# SilentStepStick-TMC2130_v11.net
KiCad netlist of a schematic drawn in EAGLE
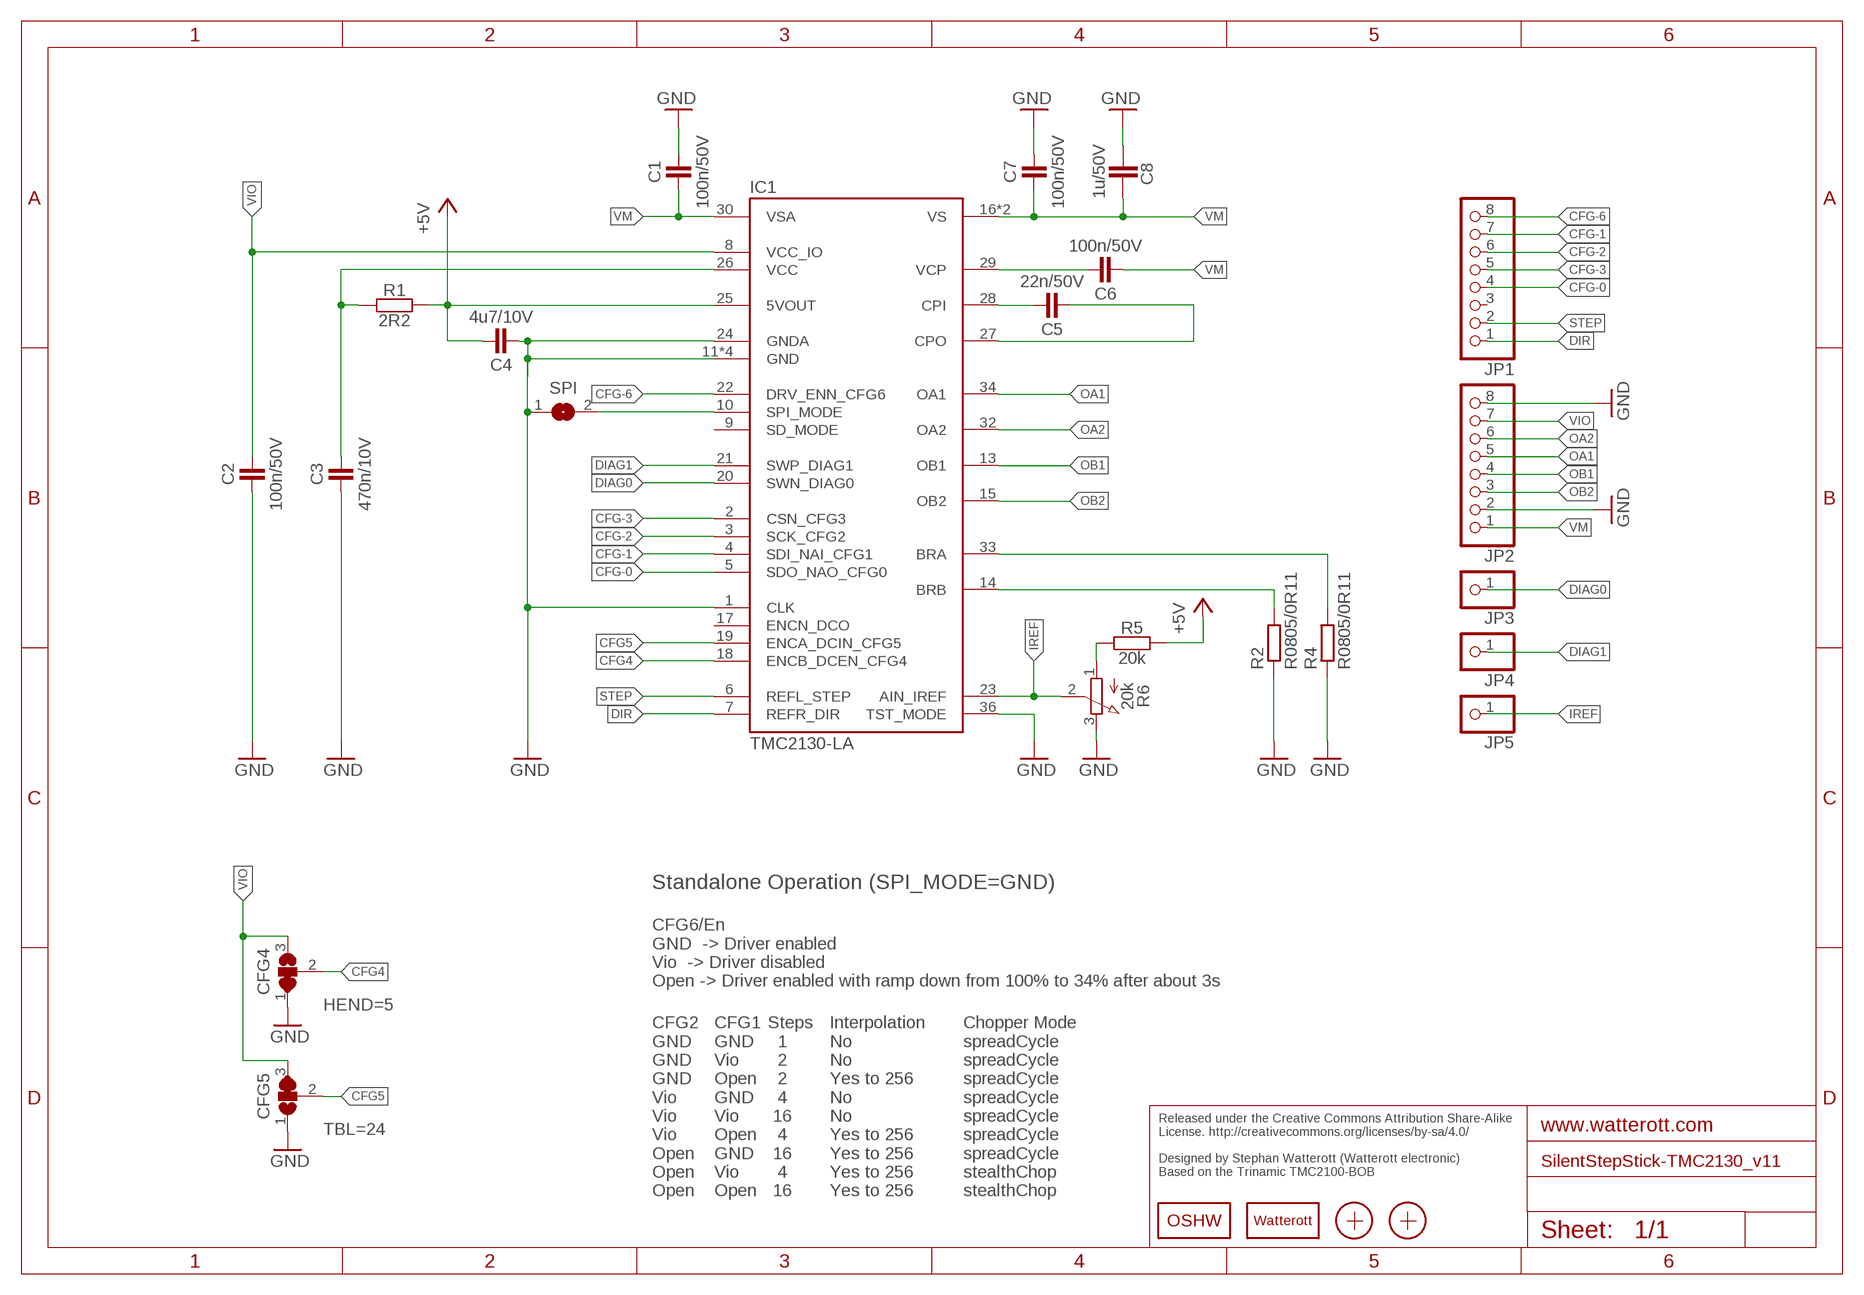
[diagram p0: schematic, sheet 1]

(export (version "E")
  (design (tool "Eeschema 10.0.6"))
  (components
    (comp (ref "C1")
      (value "100n/50V")
      (footprint "eagle-import:C0402")
      (libsource (lib "eagle-import") (part "CAPACITOR-0402"))
    )
    (comp (ref "C2")
      (value "100n/50V")
      (footprint "eagle-import:C0402")
      (libsource (lib "eagle-import") (part "CAPACITOR-0402"))
    )
    (comp (ref "C3")
      (value "470n/10V")
      (footprint "eagle-import:C0402")
      (libsource (lib "eagle-import") (part "CAPACITOR-0402"))
    )
    (comp (ref "C4")
      (value "4u7/10V")
      (footprint "eagle-import:C0402")
      (libsource (lib "eagle-import") (part "CAPACITOR-0402"))
    )
    (comp (ref "C5")
      (value "22n/50V")
      (footprint "eagle-import:C0402")
      (libsource (lib "eagle-import") (part "CAPACITOR-0402"))
    )
    (comp (ref "C6")
      (value "100n/50V")
      (footprint "eagle-import:C0402")
      (libsource (lib "eagle-import") (part "CAPACITOR-0402"))
    )
    (comp (ref "C7")
      (value "100n/50V")
      (footprint "eagle-import:C0402")
      (libsource (lib "eagle-import") (part "CAPACITOR-0402"))
    )
    (comp (ref "C8")
      (value "1u/50V")
      (footprint "eagle-import:C0603")
      (libsource (lib "eagle-import") (part "C-EUC0603"))
    )
    (comp (ref "CFG4")
      (value "JUMPER3-0201")
      (footprint "eagle-import:JUMPER3-0201")
      (libsource (lib "eagle-import") (part "JUMPER3-0201"))
    )
    (comp (ref "CFG5")
      (value "JUMPER3-0201")
      (footprint "eagle-import:JUMPER3-0201")
      (libsource (lib "eagle-import") (part "JUMPER3-0201"))
    )
    (comp (ref "IC1")
      (value "TMC2130-LA")
      (footprint "eagle-import:QFN36-PAD")
      (libsource (lib "eagle-import") (part "TMC21X0-LA"))
    )
    (comp (ref "JP1")
      (value "PINHD-1X08_2.54-S")
      (footprint "eagle-import:1X08-S")
      (libsource (lib "eagle-import") (part "PINHD-1X08_2.54-S"))
    )
    (comp (ref "JP2")
      (value "PINHD-1X08_2.54-S")
      (footprint "eagle-import:1X08-S")
      (libsource (lib "eagle-import") (part "PINHD-1X08_2.54-S"))
    )
    (comp (ref "JP3")
      (value "PINHD-1X1")
      (footprint "eagle-import:1X01")
      (libsource (lib "eagle-import") (part "PINHD-1X1"))
    )
    (comp (ref "JP4")
      (value "PINHD-1X1")
      (footprint "eagle-import:1X01")
      (libsource (lib "eagle-import") (part "PINHD-1X1"))
    )
    (comp (ref "JP5")
      (value "PINHD-1X1")
      (footprint "eagle-import:1X01")
      (libsource (lib "eagle-import") (part "PINHD-1X1"))
    )
    (comp (ref "LOGO1")
      (value "OSHW_LOGOX0070")
      (footprint "eagle-import:OSHW_6X70")
      (libsource (lib "eagle-import") (part "OSHW_LOGOX0070"))
    )
    (comp (ref "LOGO2")
      (value "LOGO-S_PLACE_M")
      (footprint "eagle-import:SPARK_TPLACE_M")
      (libsource (lib "eagle-import") (part "LOGO-S_PLACE_M"))
    )
    (comp (ref "R1")
      (value "2R2")
      (footprint "eagle-import:C0402")
      (libsource (lib "eagle-import") (part "RESISTOR-0402"))
    )
    (comp (ref "R2")
      (value "R0805/0R11")
      (footprint "eagle-import:M0805")
      (libsource (lib "eagle-import") (part "R-EU_M0805"))
    )
    (comp (ref "R4")
      (value "R0805/0R11")
      (footprint "eagle-import:M0805")
      (libsource (lib "eagle-import") (part "R-EU_M0805"))
    )
    (comp (ref "R5")
      (value "20k")
      (footprint "eagle-import:C0402")
      (libsource (lib "eagle-import") (part "RESISTOR-0402"))
    )
    (comp (ref "R6")
      (value "20k")
      (footprint "eagle-import:POT_EVM3R")
      (libsource (lib "eagle-import") (part "POT-EVM3R"))
    )
    (comp (ref "SPI")
      (value "JUMPER2-0402-NC")
      (footprint "eagle-import:JUMPER2-0402_NC")
      (libsource (lib "eagle-import") (part "JUMPER2-0402-NC"))
    )
    (comp (ref "X1")
      (value "PASSER-07")
      (footprint "eagle-import:PASSER_07MM")
      (libsource (lib "eagle-import") (part "PASSER-07"))
    )
    (comp (ref "X2")
      (value "PASSER-07")
      (footprint "eagle-import:PASSER_07MM")
      (libsource (lib "eagle-import") (part "PASSER-07"))
    )
  )
  (nets
    (net (code "1") (name "+5V") (class "Default")
      (node (ref "C4") (pin "2") (pinfunction "2_2") (pintype "passive"))
      (node (ref "IC1") (pin "25") (pinfunction "5VOUT_25") (pintype "power_in"))
      (node (ref "R1") (pin "2") (pinfunction "2_2") (pintype "passive"))
      (node (ref "R5") (pin "2") (pinfunction "2_2") (pintype "passive"))
    )
    (net (code "2") (name "CFG-0") (class "Default")
      (node (ref "IC1") (pin "5") (pinfunction "SDO_NAO_CFG0_5") (pintype "bidirectional"))
      (node (ref "JP1") (pin "4") (pinfunction "4_4") (pintype "passive"))
    )
    (net (code "3") (name "CFG-1") (class "Default")
      (node (ref "IC1") (pin "4") (pinfunction "SDI_NAI_CFG1_4") (pintype "bidirectional"))
      (node (ref "JP1") (pin "7") (pinfunction "7_7") (pintype "passive"))
    )
    (net (code "4") (name "CFG-2") (class "Default")
      (node (ref "IC1") (pin "3") (pinfunction "SCK_CFG2_3") (pintype "bidirectional"))
      (node (ref "JP1") (pin "6") (pinfunction "6_6") (pintype "passive"))
    )
    (net (code "5") (name "CFG-3") (class "Default")
      (node (ref "IC1") (pin "2") (pinfunction "CSN_CFG3_2") (pintype "bidirectional"))
      (node (ref "JP1") (pin "5") (pinfunction "5_5") (pintype "passive"))
    )
    (net (code "6") (name "CFG-6") (class "Default")
      (node (ref "IC1") (pin "22") (pinfunction "DRV_ENN_CFG6_22") (pintype "bidirectional"))
      (node (ref "JP1") (pin "8") (pinfunction "8_8") (pintype "passive"))
    )
    (net (code "7") (name "CFG4") (class "Default")
      (node (ref "CFG4") (pin "2") (pinfunction "2_2") (pintype "passive"))
      (node (ref "IC1") (pin "18") (pinfunction "ENCB_DCEN_CFG4_18") (pintype "bidirectional"))
    )
    (net (code "8") (name "CFG5") (class "Default")
      (node (ref "CFG5") (pin "2") (pinfunction "2_2") (pintype "passive"))
      (node (ref "IC1") (pin "19") (pinfunction "ENCA_DCIN_CFG5_19") (pintype "bidirectional"))
    )
    (net (code "9") (name "DIAG0") (class "Default")
      (node (ref "IC1") (pin "20") (pinfunction "SWN_DIAG0_20") (pintype "bidirectional"))
      (node (ref "JP3") (pin "1") (pinfunction "1_1") (pintype "passive"))
    )
    (net (code "10") (name "DIAG1") (class "Default")
      (node (ref "IC1") (pin "21") (pinfunction "SWP_DIAG1_21") (pintype "bidirectional"))
      (node (ref "JP4") (pin "1") (pinfunction "1_1") (pintype "passive"))
    )
    (net (code "11") (name "DIR") (class "Default")
      (node (ref "IC1") (pin "7") (pinfunction "REFR_DIR_7") (pintype "bidirectional"))
      (node (ref "JP1") (pin "1") (pinfunction "1_1") (pintype "passive"))
    )
    (net (code "12") (name "GND") (class "Default")
      (node (ref "C1") (pin "2") (pinfunction "2_2") (pintype "passive"))
      (node (ref "C2") (pin "1") (pinfunction "1_1") (pintype "passive"))
      (node (ref "C3") (pin "1") (pinfunction "1_1") (pintype "passive"))
      (node (ref "C4") (pin "1") (pinfunction "1_1") (pintype "passive"))
      (node (ref "C7") (pin "2") (pinfunction "2_2") (pintype "passive"))
      (node (ref "C8") (pin "2") (pinfunction "2_2") (pintype "passive"))
      (node (ref "CFG4") (pin "1") (pinfunction "1_1") (pintype "passive"))
      (node (ref "CFG5") (pin "1") (pinfunction "1_1") (pintype "passive"))
      (node (ref "IC1") (pin "1") (pinfunction "CLK_1") (pintype "bidirectional"))
      (node (ref "IC1") (pin "11") (pinfunction "GND_11") (pintype "power_in"))
      (node (ref "IC1") (pin "12") (pinfunction "GND_12") (pintype "power_in"))
      (node (ref "IC1") (pin "24") (pinfunction "GNDA_24") (pintype "power_in"))
      (node (ref "IC1") (pin "35") (pinfunction "GND_35") (pintype "power_in"))
      (node (ref "IC1") (pin "36") (pinfunction "TST_MODE_36") (pintype "bidirectional"))
      (node (ref "IC1") (pin "TP") (pinfunction "GND_TP") (pintype "power_in"))
      (node (ref "JP2") (pin "2") (pinfunction "2_2") (pintype "passive"))
      (node (ref "JP2") (pin "8") (pinfunction "8_8") (pintype "passive"))
      (node (ref "R2") (pin "1") (pinfunction "1_1") (pintype "passive"))
      (node (ref "R4") (pin "1") (pinfunction "1_1") (pintype "passive"))
      (node (ref "R6") (pin "3") (pinfunction "E_3") (pintype "passive"))
      (node (ref "SPI") (pin "1") (pinfunction "1_1") (pintype "passive"))
    )
    (net (code "13") (name "IREF") (class "Default")
      (node (ref "IC1") (pin "23") (pinfunction "AIN_IREF_23") (pintype "passive"))
      (node (ref "JP5") (pin "1") (pinfunction "1_1") (pintype "passive"))
      (node (ref "R6") (pin "2") (pinfunction "S_2") (pintype "passive"))
    )
    (net (code "14") (name "Net-(IC1-BRA)") (class "Default")
      (node (ref "IC1") (pin "33") (pinfunction "BRA_33") (pintype "output"))
      (node (ref "R4") (pin "2") (pinfunction "2_2") (pintype "passive"))
    )
    (net (code "15") (name "Net-(IC1-BRB)") (class "Default")
      (node (ref "IC1") (pin "14") (pinfunction "BRB_14") (pintype "output"))
      (node (ref "R2") (pin "2") (pinfunction "2_2") (pintype "passive"))
    )
    (net (code "16") (name "Net-(IC1-CPI)") (class "Default")
      (node (ref "C5") (pin "2") (pinfunction "2_2") (pintype "passive"))
      (node (ref "IC1") (pin "28") (pinfunction "CPI_28") (pintype "passive"))
    )
    (net (code "17") (name "Net-(IC1-CPO)") (class "Default")
      (node (ref "C5") (pin "1") (pinfunction "1_1") (pintype "passive"))
      (node (ref "IC1") (pin "27") (pinfunction "CPO_27") (pintype "passive"))
    )
    (net (code "18") (name "Net-(IC1-SPI_MODE)") (class "Default")
      (node (ref "IC1") (pin "10") (pinfunction "SPI_MODE_10") (pintype "bidirectional"))
      (node (ref "SPI") (pin "2") (pinfunction "2_2") (pintype "passive"))
    )
    (net (code "19") (name "Net-(IC1-VCC)") (class "Default")
      (node (ref "C3") (pin "2") (pinfunction "2_2") (pintype "passive"))
      (node (ref "IC1") (pin "26") (pinfunction "VCC_26") (pintype "power_in"))
      (node (ref "R1") (pin "1") (pinfunction "1_1") (pintype "passive"))
    )
    (net (code "20") (name "Net-(IC1-VCP)") (class "Default")
      (node (ref "C6") (pin "2") (pinfunction "2_2") (pintype "passive"))
      (node (ref "IC1") (pin "29") (pinfunction "VCP_29") (pintype "passive"))
    )
    (net (code "21") (name "Net-(R6-A)") (class "Default")
      (node (ref "R5") (pin "1") (pinfunction "1_1") (pintype "passive"))
      (node (ref "R6") (pin "1") (pinfunction "A_1") (pintype "passive"))
    )
    (net (code "22") (name "OA1") (class "Default")
      (node (ref "IC1") (pin "34") (pinfunction "OA1_34") (pintype "output"))
      (node (ref "JP2") (pin "5") (pinfunction "5_5") (pintype "passive"))
    )
    (net (code "23") (name "OA2") (class "Default")
      (node (ref "IC1") (pin "32") (pinfunction "OA2_32") (pintype "output"))
      (node (ref "JP2") (pin "6") (pinfunction "6_6") (pintype "passive"))
    )
    (net (code "24") (name "OB1") (class "Default")
      (node (ref "IC1") (pin "13") (pinfunction "OB1_13") (pintype "output"))
      (node (ref "JP2") (pin "4") (pinfunction "4_4") (pintype "passive"))
    )
    (net (code "25") (name "OB2") (class "Default")
      (node (ref "IC1") (pin "15") (pinfunction "OB2_15") (pintype "output"))
      (node (ref "JP2") (pin "3") (pinfunction "3_3") (pintype "passive"))
    )
    (net (code "26") (name "STEP") (class "Default")
      (node (ref "IC1") (pin "6") (pinfunction "REFL_STEP_6") (pintype "bidirectional"))
      (node (ref "JP1") (pin "2") (pinfunction "2_2") (pintype "passive"))
    )
    (net (code "27") (name "VIO") (class "Default")
      (node (ref "C2") (pin "2") (pinfunction "2_2") (pintype "passive"))
      (node (ref "CFG4") (pin "3") (pinfunction "3_3") (pintype "passive"))
      (node (ref "CFG5") (pin "3") (pinfunction "3_3") (pintype "passive"))
      (node (ref "IC1") (pin "8") (pinfunction "VCC_IO_8") (pintype "power_in"))
      (node (ref "JP2") (pin "7") (pinfunction "7_7") (pintype "passive"))
    )
    (net (code "28") (name "VM") (class "Default")
      (node (ref "C1") (pin "1") (pinfunction "1_1") (pintype "passive"))
      (node (ref "C6") (pin "1") (pinfunction "1_1") (pintype "passive"))
      (node (ref "C7") (pin "1") (pinfunction "1_1") (pintype "passive"))
      (node (ref "C8") (pin "1") (pinfunction "1_1") (pintype "passive"))
      (node (ref "IC1") (pin "16") (pinfunction "VS_16") (pintype "power_in"))
      (node (ref "IC1") (pin "30") (pinfunction "VSA_30") (pintype "power_in"))
      (node (ref "IC1") (pin "31") (pinfunction "VS_31") (pintype "power_in"))
      (node (ref "JP2") (pin "1") (pinfunction "1_1") (pintype "passive"))
    )
    (net (code "29") (name "unconnected-(IC1-ENCN_DCO-Pad17)") (class "Default")
      (node (ref "IC1") (pin "17") (pinfunction "ENCN_DCO_17") (pintype "bidirectional"))
    )
    (net (code "30") (name "unconnected-(IC1-SD_MODE-Pad9)") (class "Default")
      (node (ref "IC1") (pin "9") (pinfunction "SD_MODE_9") (pintype "bidirectional"))
    )
    (net (code "31") (name "unconnected-(JP1-Pad3)") (class "Default")
      (node (ref "JP1") (pin "3") (pinfunction "3_3") (pintype "passive"))
    )
  )
)
